# KitchenTimerFullDig.net
KiCad netlist of a schematic drawn in Altium Designer
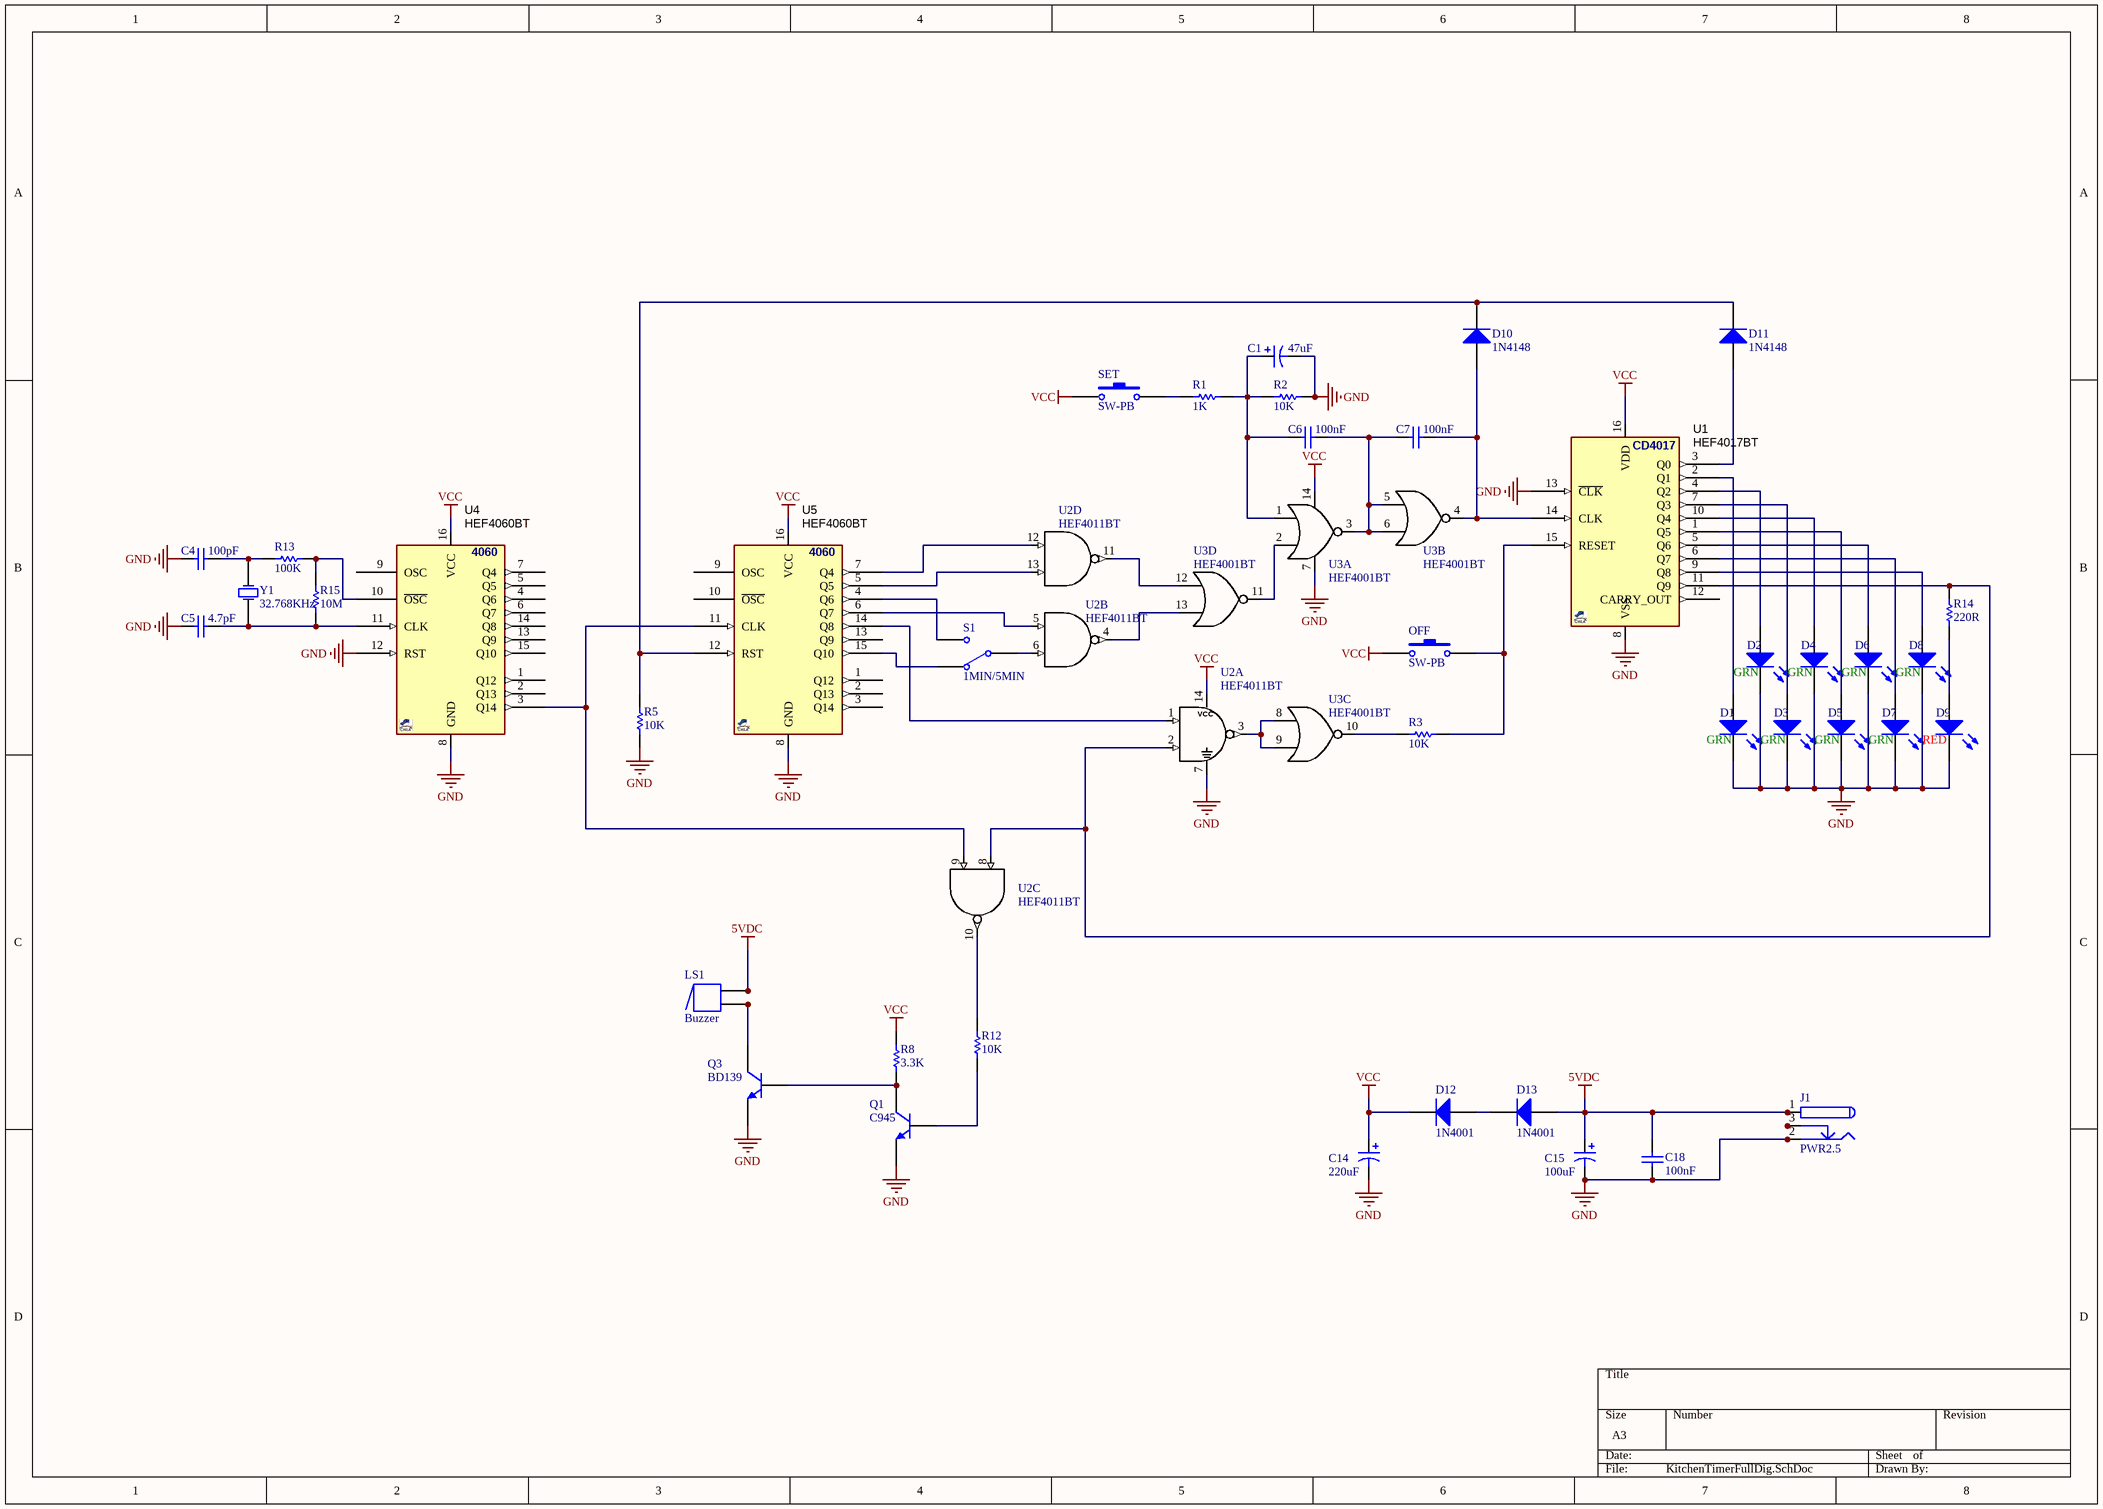
[diagram p0: KitchenTimerFullDig.SchDoc]

(export (version "E")
  (design (tool "Eeschema 10.0.6"))
  (components
    (comp (ref "C1")
      (value "47uF")
      (footprint "A")
      (description "Polarized Capacitor (Radial)")
      (fields (field (name "Comment") "Cap Pol1") (field (name "PUBLISHER") "Altium Limited"))
      (libsource (lib "Miscellaneous Devices") (part "Cap Pol1"))
    )
    (comp (ref "C4")
      (value "100pF")
      (footprint "CAP100N")
      (description "Capacitor")
      (fields (field (name "Comment") "Cap") (field (name "PUBLISHER") "Altium Limited"))
      (libsource (lib "Miscellaneous Devices") (part "Cap"))
    )
    (comp (ref "C5")
      (value "4.7pF")
      (footprint "CAP100N")
      (description "Capacitor")
      (fields (field (name "Comment") "Cap") (field (name "PUBLISHER") "Altium Limited"))
      (libsource (lib "Miscellaneous Devices") (part "Cap"))
    )
    (comp (ref "C6")
      (value "100nF")
      (footprint "CAP100N")
      (description "Capacitor")
      (fields (field (name "Comment") "Cap") (field (name "PUBLISHER") "Altium Limited"))
      (libsource (lib "Miscellaneous Devices") (part "Cap"))
    )
    (comp (ref "C7")
      (value "100nF")
      (footprint "CAP100N")
      (description "Capacitor")
      (fields (field (name "Comment") "Cap") (field (name "PUBLISHER") "Altium Limited"))
      (libsource (lib "Miscellaneous Devices") (part "Cap"))
    )
    (comp (ref "C14")
      (value "220uF")
      (footprint "A")
      (description "Polarized Capacitor (Radial)")
      (fields (field (name "Comment") "Cap Pol1") (field (name "PUBLISHER") "Altium Limited"))
      (libsource (lib "Miscellaneous Devices") (part "Cap Pol1"))
    )
    (comp (ref "C15")
      (value "100uF")
      (footprint "A")
      (description "Polarized Capacitor (Radial)")
      (fields (field (name "Comment") "Cap Pol1") (field (name "PUBLISHER") "Altium Limited"))
      (libsource (lib "Miscellaneous Devices") (part "Cap Pol1"))
    )
    (comp (ref "C18")
      (value "100nF")
      (footprint "CAP100N")
      (description "Capacitor")
      (fields (field (name "Comment") "Cap") (field (name "PUBLISHER") "Altium Limited"))
      (libsource (lib "Miscellaneous Devices") (part "Cap"))
    )
    (comp (ref "D1")
      (value "GRN")
      (footprint "LED3MM")
      (description "Typical INFRARED GaAs LED")
      (fields (field (name "PUBLISHER") "Altium Limited"))
      (libsource (lib "Miscellaneous Devices") (part "LED0"))
    )
    (comp (ref "D2")
      (value "GRN")
      (footprint "LED3MM")
      (description "Typical INFRARED GaAs LED")
      (fields (field (name "PUBLISHER") "Altium Limited"))
      (libsource (lib "Miscellaneous Devices") (part "LED0"))
    )
    (comp (ref "D3")
      (value "GRN")
      (footprint "LED3MM")
      (description "Typical INFRARED GaAs LED")
      (fields (field (name "PUBLISHER") "Altium Limited"))
      (libsource (lib "Miscellaneous Devices") (part "LED0"))
    )
    (comp (ref "D4")
      (value "GRN")
      (footprint "LED3MM")
      (description "Typical INFRARED GaAs LED")
      (fields (field (name "PUBLISHER") "Altium Limited"))
      (libsource (lib "Miscellaneous Devices") (part "LED0"))
    )
    (comp (ref "D5")
      (value "GRN")
      (footprint "LED3MM")
      (description "Typical INFRARED GaAs LED")
      (fields (field (name "PUBLISHER") "Altium Limited"))
      (libsource (lib "Miscellaneous Devices") (part "LED0"))
    )
    (comp (ref "D6")
      (value "GRN")
      (footprint "LED3MM")
      (description "Typical INFRARED GaAs LED")
      (fields (field (name "PUBLISHER") "Altium Limited"))
      (libsource (lib "Miscellaneous Devices") (part "LED0"))
    )
    (comp (ref "D7")
      (value "GRN")
      (footprint "LED3MM")
      (description "Typical INFRARED GaAs LED")
      (fields (field (name "PUBLISHER") "Altium Limited"))
      (libsource (lib "Miscellaneous Devices") (part "LED0"))
    )
    (comp (ref "D8")
      (value "GRN")
      (footprint "LED3MM")
      (description "Typical INFRARED GaAs LED")
      (fields (field (name "PUBLISHER") "Altium Limited"))
      (libsource (lib "Miscellaneous Devices") (part "LED0"))
    )
    (comp (ref "D9")
      (value "RED")
      (footprint "LED3MM")
      (description "Typical INFRARED GaAs LED")
      (fields (field (name "PUBLISHER") "Altium Limited"))
      (libsource (lib "Miscellaneous Devices") (part "LED0"))
    )
    (comp (ref "D10")
      (value "1N4148")
      (footprint "D_LN")
      (description "High Conductance Fast Diode")
      (fields (field (name "PUBLISHER") "Altium Limited"))
      (libsource (lib "Miscellaneous Devices") (part "Diode 1N4148"))
    )
    (comp (ref "D11")
      (value "1N4148")
      (footprint "D_LN")
      (description "High Conductance Fast Diode")
      (fields (field (name "PUBLISHER") "Altium Limited"))
      (libsource (lib "Miscellaneous Devices") (part "Diode 1N4148"))
    )
    (comp (ref "D12")
      (value "1N4001")
      (footprint "DO-35")
      (description "High Conductance Fast Diode")
      (fields (field (name "PUBLISHER") "Altium Limited"))
      (libsource (lib "Miscellaneous Devices") (part "Diode 1N4148"))
    )
    (comp (ref "D13")
      (value "1N4001")
      (footprint "DO-35")
      (description "High Conductance Fast Diode")
      (fields (field (name "PUBLISHER") "Altium Limited"))
      (libsource (lib "Miscellaneous Devices") (part "Diode 1N4148"))
    )
    (comp (ref "J1")
      (value "PWR2.5")
      (footprint "KLD-0202")
      (description "Low Voltage Power Supply Connector")
      (fields (field (name "PUBLISHER") "Altium Limited"))
      (libsource (lib "Miscellaneous Connectors") (part "PWR2.5"))
    )
    (comp (ref "LS1")
      (value "Buzzer")
      (footprint "ABSM-1574")
      (description "Magnetic Transducer Buzzer")
      (fields (field (name "PUBLISHER") "Altium Limited"))
      (libsource (lib "Miscellaneous Devices") (part "Buzzer"))
    )
    (comp (ref "OFF")
      (value "SW-PB")
      (footprint "BUTTN")
      (description "Switch")
      (fields (field (name "PUBLISHER") "Altium Limited"))
      (libsource (lib "Miscellaneous Devices") (part "SW-PB"))
    )
    (comp (ref "Q1")
      (value "C945")
      (footprint "TO-92")
      (description "NPN Bipolar Transistor")
      (fields (field (name "PUBLISHER") "Altium Limited"))
      (libsource (lib "Miscellaneous Devices") (part "NPN"))
    )
    (comp (ref "Q3")
      (value "BD139")
      (footprint "BD139")
      (description "NPN Bipolar Transistor")
      (fields (field (name "PUBLISHER") "Altium Limited"))
      (libsource (lib "Miscellaneous Devices") (part "NPN"))
    )
    (comp (ref "R1")
      (value "1K")
      (footprint "AXIAL-0.3")
      (description "Resistor")
      (fields (field (name "Comment") "Res1") (field (name "PUBLISHER") "Altium Limited"))
      (libsource (lib "Miscellaneous Devices") (part "Res1"))
    )
    (comp (ref "R2")
      (value "10K")
      (footprint "AXIAL-0.3")
      (description "Resistor")
      (fields (field (name "Comment") "Res1") (field (name "PUBLISHER") "Altium Limited"))
      (libsource (lib "Miscellaneous Devices") (part "Res1"))
    )
    (comp (ref "R3")
      (value "10K")
      (footprint "AXIAL-0.3")
      (description "Resistor")
      (fields (field (name "Comment") "Res1") (field (name "PUBLISHER") "Altium Limited"))
      (libsource (lib "Miscellaneous Devices") (part "Res1"))
    )
    (comp (ref "R5")
      (value "10K")
      (footprint "AXIAL-0.3")
      (description "Resistor")
      (fields (field (name "Comment") "Res1") (field (name "PUBLISHER") "Altium Limited"))
      (libsource (lib "Miscellaneous Devices") (part "Res1"))
    )
    (comp (ref "R8")
      (value "3.3K")
      (footprint "AXIAL-0.3")
      (description "Resistor")
      (fields (field (name "Comment") "Res1") (field (name "PUBLISHER") "Altium Limited"))
      (libsource (lib "Miscellaneous Devices") (part "Res1"))
    )
    (comp (ref "R12")
      (value "10K")
      (footprint "AXIAL-0.3")
      (description "Resistor")
      (fields (field (name "Comment") "Res1") (field (name "PUBLISHER") "Altium Limited"))
      (libsource (lib "Miscellaneous Devices") (part "Res1"))
    )
    (comp (ref "R13")
      (value "100K")
      (footprint "AXIAL-0.3")
      (description "Resistor")
      (fields (field (name "Comment") "Res1") (field (name "PUBLISHER") "Altium Limited"))
      (libsource (lib "Miscellaneous Devices") (part "Res1"))
    )
    (comp (ref "R14")
      (value "220R")
      (footprint "AXIAL-0.3")
      (description "Resistor")
      (fields (field (name "Comment") "Res1") (field (name "PUBLISHER") "Altium Limited"))
      (libsource (lib "Miscellaneous Devices") (part "Res1"))
    )
    (comp (ref "R15")
      (value "10M")
      (footprint "AXIAL-0.3")
      (description "Resistor")
      (fields (field (name "Comment") "Res1") (field (name "PUBLISHER") "Altium Limited"))
      (libsource (lib "Miscellaneous Devices") (part "Res1"))
    )
    (comp (ref "S1")
      (value "1MIN/5MIN")
      (footprint "TL36WW15050")
      (description "SPDT Subminiature Toggle Switch, Right Angle Mounting, Vertical Actuation")
      (fields (field (name "PUBLISHER") "Altium Limited"))
      (libsource (lib "Miscellaneous Devices") (part "SW-SPDT"))
    )
    (comp (ref "SET")
      (value "SW-PB")
      (footprint "BUTTN")
      (description "Switch")
      (fields (field (name "PUBLISHER") "Altium Limited"))
      (libsource (lib "Miscellaneous Devices") (part "SW-PB"))
    )
    (comp (ref "U1")
      (value "HEF4017BT")
      (footprint "SO_16")
      (description "Counter, 10 decoded output")
      (fields (field (name "MANF") "TI") (field (name "MANF_P#") "CD4017BE"))
      (libsource (lib "logic_counter") (part "CD4017_DIP16"))
    )
    (comp (ref "U2")
      (value "HEF4011BT")
      (footprint "SO_14")
      (description "GATE, NAND, Quad 2-Input")
      (fields (field (name "MANF_P#") "CD4011BCMA"))
      (libsource (lib "logic_gate") (part "NANDx4_CD4011BCM"))
    )
    (comp (ref "U3")
      (value "HEF4001BT")
      (footprint "SO_14")
      (description "Gate, NOR, Quad 2 Input")
      (fields (field (name "MANF") "Texas Instruments") (field (name "MANF_P#") "CD74HC02E"))
      (libsource (lib "KitchenTimerBoard") (part "NORx4_CD74HC02_DIP"))
    )
    (comp (ref "U4")
      (value "HEF4060BT")
      (footprint "SO_16")
      (description "Counter, 14-Bit Binary, 3~18v, 10mA")
      (fields (field (name "MANF") "TI") (field (name "MANF_P#") "CD4060BE"))
      (libsource (lib "logic_counter") (part "CD4060_DIP16"))
    )
    (comp (ref "U5")
      (value "HEF4060BT")
      (footprint "SO_16")
      (description "Counter, 14-Bit Binary, 3~18v, 10mA")
      (fields (field (name "MANF") "TI") (field (name "MANF_P#") "CD4060BE"))
      (libsource (lib "logic_counter") (part "CD4060_DIP16"))
    )
    (comp (ref "Y1")
      (value "32.768KHz")
      (footprint "XTAL")
      (description "Crystal Oscillator")
      (fields (field (name "Comment") "ECS-040-20-4X-DU") (field (name "PUBLISHER") "Altium Limited"))
      (libsource (lib "AXC-WS1") (part "XTAL"))
    )
  )
  (nets
    (net (code "1") (name "5VDC") (class "Default")
      (node (ref "C15") (pin "1") (pinfunction "1_1") (pintype "passive"))
      (node (ref "C18") (pin "2") (pinfunction "2_2") (pintype "passive"))
      (node (ref "D13") (pin "1") (pinfunction "A_1") (pintype "passive"))
      (node (ref "J1") (pin "1") (pinfunction "1_1") (pintype "power_in"))
      (node (ref "J1") (pin "1A") (pinfunction "1A_1A") (pintype "power_in"))
      (node (ref "J1") (pin "1B") (pinfunction "1B_1B") (pintype "power_in"))
      (node (ref "LS1") (pin "1") (pinfunction "1_1") (pintype "passive"))
      (node (ref "LS1") (pin "1A") (pinfunction "1A_1A") (pintype "passive"))
    )
    (net (code "2") (name "GND") (class "Default")
      (node (ref "C1") (pin "2") (pinfunction "2_2") (pintype "passive"))
      (node (ref "C14") (pin "2") (pinfunction "2_2") (pintype "passive"))
      (node (ref "C15") (pin "2") (pinfunction "2_2") (pintype "passive"))
      (node (ref "C18") (pin "1") (pinfunction "1_1") (pintype "passive"))
      (node (ref "C4") (pin "1") (pinfunction "1_1") (pintype "passive"))
      (node (ref "C5") (pin "1") (pinfunction "1_1") (pintype "passive"))
      (node (ref "D1") (pin "2") (pinfunction "K_2") (pintype "passive"))
      (node (ref "D2") (pin "2") (pinfunction "K_2") (pintype "passive"))
      (node (ref "D3") (pin "2") (pinfunction "K_2") (pintype "passive"))
      (node (ref "D4") (pin "2") (pinfunction "K_2") (pintype "passive"))
      (node (ref "D5") (pin "2") (pinfunction "K_2") (pintype "passive"))
      (node (ref "D6") (pin "2") (pinfunction "K_2") (pintype "passive"))
      (node (ref "D7") (pin "2") (pinfunction "K_2") (pintype "passive"))
      (node (ref "D8") (pin "2") (pinfunction "K_2") (pintype "passive"))
      (node (ref "D9") (pin "2") (pinfunction "K_2") (pintype "passive"))
      (node (ref "J1") (pin "2") (pinfunction "2_2") (pintype "power_in"))
      (node (ref "J1") (pin "2A") (pinfunction "2A_2A") (pintype "power_in"))
      (node (ref "J1") (pin "2B") (pinfunction "2B_2B") (pintype "power_in"))
      (node (ref "Q1") (pin "3") (pinfunction "E_3") (pintype "passive"))
      (node (ref "Q3") (pin "3") (pinfunction "E_3") (pintype "passive"))
      (node (ref "R2") (pin "2") (pinfunction "2_2") (pintype "passive"))
      (node (ref "R5") (pin "2") (pinfunction "2_2") (pintype "passive"))
      (node (ref "U1") (pin "13") (pinfunction "~{CLK}_13") (pintype "input"))
      (node (ref "U1") (pin "8") (pinfunction "VSS_8") (pintype "power_in"))
      (node (ref "U2") (pin "7") (pinfunction "GND_7") (pintype "power_in"))
      (node (ref "U3") (pin "7") (pinfunction "GND_7") (pintype "passive"))
      (node (ref "U4") (pin "12") (pinfunction "RST_12") (pintype "input"))
      (node (ref "U4") (pin "8") (pinfunction "GND_8") (pintype "power_in"))
      (node (ref "U5") (pin "8") (pinfunction "GND_8") (pintype "power_in"))
    )
    (net (code "3") (name "Net-(C1-Pad1)") (class "Default")
      (node (ref "C1") (pin "1") (pinfunction "1_1") (pintype "passive"))
      (node (ref "C6") (pin "1") (pinfunction "1_1") (pintype "passive"))
      (node (ref "R1") (pin "2") (pinfunction "2_2") (pintype "passive"))
      (node (ref "R2") (pin "1") (pinfunction "1_1") (pintype "passive"))
      (node (ref "U3") (pin "1") (pinfunction "1_1") (pintype "passive"))
    )
    (net (code "4") (name "Net-(C6-Pad2)") (class "Default")
      (node (ref "C6") (pin "2") (pinfunction "2_2") (pintype "passive"))
      (node (ref "C7") (pin "1") (pinfunction "1_1") (pintype "passive"))
      (node (ref "U3") (pin "3") (pinfunction "3_3") (pintype "passive"))
      (node (ref "U3") (pin "5") (pinfunction "5_5") (pintype "passive"))
      (node (ref "U3") (pin "6") (pinfunction "6_6") (pintype "passive"))
    )
    (net (code "5") (name "Net-(D1-A)") (class "Default")
      (node (ref "D1") (pin "1") (pinfunction "A_1") (pintype "passive"))
      (node (ref "U1") (pin "2") (pinfunction "Q1_2") (pintype "output"))
    )
    (net (code "6") (name "Net-(D2-A)") (class "Default")
      (node (ref "D2") (pin "1") (pinfunction "A_1") (pintype "passive"))
      (node (ref "U1") (pin "4") (pinfunction "Q2_4") (pintype "output"))
    )
    (net (code "7") (name "Net-(D3-A)") (class "Default")
      (node (ref "D3") (pin "1") (pinfunction "A_1") (pintype "passive"))
      (node (ref "U1") (pin "7") (pinfunction "Q3_7") (pintype "output"))
    )
    (net (code "8") (name "Net-(D4-A)") (class "Default")
      (node (ref "D4") (pin "1") (pinfunction "A_1") (pintype "passive"))
      (node (ref "U1") (pin "10") (pinfunction "Q4_10") (pintype "output"))
    )
    (net (code "9") (name "Net-(D5-A)") (class "Default")
      (node (ref "D5") (pin "1") (pinfunction "A_1") (pintype "passive"))
      (node (ref "U1") (pin "1") (pinfunction "Q5_1") (pintype "output"))
    )
    (net (code "10") (name "Net-(D6-A)") (class "Default")
      (node (ref "D6") (pin "1") (pinfunction "A_1") (pintype "passive"))
      (node (ref "U1") (pin "5") (pinfunction "Q6_5") (pintype "output"))
    )
    (net (code "11") (name "Net-(D7-A)") (class "Default")
      (node (ref "D7") (pin "1") (pinfunction "A_1") (pintype "passive"))
      (node (ref "U1") (pin "6") (pinfunction "Q7_6") (pintype "output"))
    )
    (net (code "12") (name "Net-(D8-A)") (class "Default")
      (node (ref "D8") (pin "1") (pinfunction "A_1") (pintype "passive"))
      (node (ref "U1") (pin "9") (pinfunction "Q8_9") (pintype "output"))
    )
    (net (code "13") (name "Net-(D9-A)") (class "Default")
      (node (ref "D9") (pin "1") (pinfunction "A_1") (pintype "passive"))
      (node (ref "R14") (pin "1") (pinfunction "1_1") (pintype "passive"))
    )
    (net (code "14") (name "Net-(D10-A)") (class "Default")
      (node (ref "C7") (pin "2") (pinfunction "2_2") (pintype "passive"))
      (node (ref "D10") (pin "1") (pinfunction "A_1") (pintype "passive"))
      (node (ref "U1") (pin "14") (pinfunction "CLK_14") (pintype "input"))
      (node (ref "U3") (pin "4") (pinfunction "4_4") (pintype "passive"))
    )
    (net (code "15") (name "Net-(D10-K)") (class "Default")
      (node (ref "D10") (pin "2") (pinfunction "K_2") (pintype "passive"))
      (node (ref "D11") (pin "2") (pinfunction "K_2") (pintype "passive"))
      (node (ref "R5") (pin "1") (pinfunction "1_1") (pintype "passive"))
      (node (ref "U5") (pin "12") (pinfunction "RST_12") (pintype "input"))
    )
    (net (code "16") (name "Net-(D11-A)") (class "Default")
      (node (ref "D11") (pin "1") (pinfunction "A_1") (pintype "passive"))
      (node (ref "U1") (pin "3") (pinfunction "Q0_3") (pintype "output"))
    )
    (net (code "17") (name "Net-(D12-A)") (class "Default")
      (node (ref "D12") (pin "1") (pinfunction "A_1") (pintype "passive"))
      (node (ref "D13") (pin "2") (pinfunction "K_2") (pintype "passive"))
    )
    (net (code "18") (name "Net-(J1-Pad3)") (class "Default")
      (node (ref "J1") (pin "3") (pinfunction "3_3") (pintype "power_in"))
      (node (ref "J1") (pin "3A") (pinfunction "3A_3A") (pintype "power_in"))
      (node (ref "J1") (pin "3B") (pinfunction "3B_3B") (pintype "power_in"))
    )
    (net (code "19") (name "Net-(Q1-B)") (class "Default")
      (node (ref "Q1") (pin "2") (pinfunction "B_2") (pintype "passive"))
      (node (ref "R12") (pin "2") (pinfunction "2_2") (pintype "passive"))
    )
    (net (code "20") (name "Net-(Q1-C)") (class "Default")
      (node (ref "Q1") (pin "1") (pinfunction "C_1") (pintype "passive"))
      (node (ref "Q3") (pin "2") (pinfunction "B_2") (pintype "passive"))
      (node (ref "R8") (pin "1") (pinfunction "1_1") (pintype "passive"))
    )
    (net (code "21") (name "Net-(Q3-C)") (class "Default")
      (node (ref "LS1") (pin "2") (pinfunction "2_2") (pintype "passive"))
      (node (ref "LS1") (pin "2A") (pinfunction "2A_2A") (pintype "passive"))
      (node (ref "Q3") (pin "1") (pinfunction "C_1") (pintype "passive"))
    )
    (net (code "22") (name "Net-(R1-Pad1)") (class "Default")
      (node (ref "R1") (pin "1") (pinfunction "1_1") (pintype "passive"))
      (node (ref "SET") (pin "1") (pinfunction "1_1") (pintype "passive"))
    )
    (net (code "23") (name "Net-(R3-Pad1)") (class "Default")
      (node (ref "R3") (pin "1") (pinfunction "1_1") (pintype "passive"))
      (node (ref "U3") (pin "10") (pinfunction "10_10") (pintype "passive"))
    )
    (net (code "24") (name "Net-(U1-Q9)") (class "Default")
      (node (ref "R14") (pin "2") (pinfunction "2_2") (pintype "passive"))
      (node (ref "U1") (pin "11") (pinfunction "Q9_11") (pintype "output"))
      (node (ref "U2") (pin "2") (pinfunction "B_2") (pintype "input"))
      (node (ref "U2") (pin "8") (pinfunction "A_8") (pintype "input"))
    )
    (net (code "25") (name "Net-(U1-RESET)") (class "Default")
      (node (ref "OFF") (pin "2") (pinfunction "2_2") (pintype "passive"))
      (node (ref "R3") (pin "2") (pinfunction "2_2") (pintype "passive"))
      (node (ref "U1") (pin "15") (pinfunction "RESET_15") (pintype "input"))
    )
    (net (code "26") (name "Net-(U2A-A)") (class "Default")
      (node (ref "U2") (pin "1") (pinfunction "A_1") (pintype "input"))
      (node (ref "U5") (pin "14") (pinfunction "Q8_14") (pintype "output"))
    )
    (net (code "27") (name "Net-(U2A-J)") (class "Default")
      (node (ref "U2") (pin "3") (pinfunction "J_3") (pintype "output"))
      (node (ref "U3") (pin "8") (pinfunction "8_8") (pintype "passive"))
      (node (ref "U3") (pin "9") (pinfunction "9_9") (pintype "passive"))
    )
    (net (code "28") (name "Net-(U2B-A)") (class "Default")
      (node (ref "U2") (pin "5") (pinfunction "A_5") (pintype "input"))
      (node (ref "U5") (pin "6") (pinfunction "Q7_6") (pintype "output"))
    )
    (net (code "29") (name "Net-(U2B-B)") (class "Default")
      (node (ref "S1") (pin "2") (pinfunction "2_2") (pintype "passive"))
      (node (ref "U2") (pin "6") (pinfunction "B_6") (pintype "input"))
    )
    (net (code "30") (name "Net-(U2B-J)") (class "Default")
      (node (ref "U2") (pin "4") (pinfunction "J_4") (pintype "output"))
      (node (ref "U3") (pin "13") (pinfunction "13_13") (pintype "passive"))
    )
    (net (code "31") (name "Net-(U2C-F)") (class "Default")
      (node (ref "U2") (pin "9") (pinfunction "F_9") (pintype "input"))
      (node (ref "U4") (pin "3") (pinfunction "Q14_3") (pintype "output"))
      (node (ref "U5") (pin "11") (pinfunction "CLK_11") (pintype "input"))
    )
    (net (code "32") (name "Net-(U2C-J)") (class "Default")
      (node (ref "R12") (pin "1") (pinfunction "1_1") (pintype "passive"))
      (node (ref "U2") (pin "10") (pinfunction "J_10") (pintype "output"))
    )
    (net (code "33") (name "Net-(U2D-A)") (class "Default")
      (node (ref "U2") (pin "12") (pinfunction "A_12") (pintype "input"))
      (node (ref "U5") (pin "7") (pinfunction "Q4_7") (pintype "output"))
    )
    (net (code "34") (name "Net-(U2D-B)") (class "Default")
      (node (ref "U2") (pin "13") (pinfunction "B_13") (pintype "input"))
      (node (ref "U5") (pin "5") (pinfunction "Q5_5") (pintype "output"))
    )
    (net (code "35") (name "Net-(U2D-J)") (class "Default")
      (node (ref "U2") (pin "11") (pinfunction "J_11") (pintype "output"))
      (node (ref "U3") (pin "12") (pinfunction "12_12") (pintype "passive"))
    )
    (net (code "36") (name "Net-(U3-Pad11)") (class "Default")
      (node (ref "U3") (pin "11") (pinfunction "11_11") (pintype "passive"))
      (node (ref "U3") (pin "2") (pinfunction "2_2") (pintype "passive"))
    )
    (net (code "37") (name "Net-(U4-CLK)") (class "Default")
      (node (ref "C5") (pin "2") (pinfunction "2_2") (pintype "passive"))
      (node (ref "R15") (pin "1") (pinfunction "1_1") (pintype "passive"))
      (node (ref "U4") (pin "11") (pinfunction "CLK_11") (pintype "input"))
      (node (ref "Y1") (pin "2") (pinfunction "OSC2_2") (pintype "passive"))
    )
    (net (code "38") (name "Net-(U4-~{OSC})") (class "Default")
      (node (ref "R13") (pin "2") (pinfunction "2_2") (pintype "passive"))
      (node (ref "R15") (pin "2") (pinfunction "2_2") (pintype "passive"))
      (node (ref "U4") (pin "10") (pinfunction "~{OSC}_10") (pintype "passive"))
    )
    (net (code "39") (name "Net-(U5-Q6)") (class "Default")
      (node (ref "S1") (pin "1") (pinfunction "1_1") (pintype "passive"))
      (node (ref "U5") (pin "4") (pinfunction "Q6_4") (pintype "output"))
    )
    (net (code "40") (name "Net-(U5-Q10)") (class "Default")
      (node (ref "S1") (pin "3") (pinfunction "3_3") (pintype "passive"))
      (node (ref "U5") (pin "15") (pinfunction "Q10_15") (pintype "output"))
    )
    (net (code "41") (name "Net-(Y1-OSC1)") (class "Default")
      (node (ref "C4") (pin "2") (pinfunction "2_2") (pintype "passive"))
      (node (ref "R13") (pin "1") (pinfunction "1_1") (pintype "passive"))
      (node (ref "Y1") (pin "1") (pinfunction "OSC1_1") (pintype "passive"))
    )
    (net (code "42") (name "VCC") (class "Default")
      (node (ref "C14") (pin "1") (pinfunction "1_1") (pintype "passive"))
      (node (ref "D12") (pin "2") (pinfunction "K_2") (pintype "passive"))
      (node (ref "OFF") (pin "1") (pinfunction "1_1") (pintype "passive"))
      (node (ref "R8") (pin "2") (pinfunction "2_2") (pintype "passive"))
      (node (ref "SET") (pin "2") (pinfunction "2_2") (pintype "passive"))
      (node (ref "U1") (pin "16") (pinfunction "VDD_16") (pintype "power_in"))
      (node (ref "U2") (pin "14") (pinfunction "VDD_14") (pintype "power_in"))
      (node (ref "U3") (pin "14") (pinfunction "VCC_14") (pintype "passive"))
      (node (ref "U4") (pin "16") (pinfunction "VCC_16") (pintype "power_in"))
      (node (ref "U5") (pin "16") (pinfunction "VCC_16") (pintype "power_in"))
    )
    (net (code "43") (name "unconnected-(U1-CARRY_OUT-Pad12)") (class "Default")
      (node (ref "U1") (pin "12") (pinfunction "CARRY_OUT_12") (pintype "output"))
    )
    (net (code "44") (name "unconnected-(U4-OSC-Pad9)") (class "Default")
      (node (ref "U4") (pin "9") (pinfunction "OSC_9") (pintype "passive"))
    )
    (net (code "45") (name "unconnected-(U4-Q4-Pad7)") (class "Default")
      (node (ref "U4") (pin "7") (pinfunction "Q4_7") (pintype "output"))
    )
    (net (code "46") (name "unconnected-(U4-Q5-Pad5)") (class "Default")
      (node (ref "U4") (pin "5") (pinfunction "Q5_5") (pintype "output"))
    )
    (net (code "47") (name "unconnected-(U4-Q6-Pad4)") (class "Default")
      (node (ref "U4") (pin "4") (pinfunction "Q6_4") (pintype "output"))
    )
    (net (code "48") (name "unconnected-(U4-Q7-Pad6)") (class "Default")
      (node (ref "U4") (pin "6") (pinfunction "Q7_6") (pintype "output"))
    )
    (net (code "49") (name "unconnected-(U4-Q8-Pad14)") (class "Default")
      (node (ref "U4") (pin "14") (pinfunction "Q8_14") (pintype "output"))
    )
    (net (code "50") (name "unconnected-(U4-Q9-Pad13)") (class "Default")
      (node (ref "U4") (pin "13") (pinfunction "Q9_13") (pintype "output"))
    )
    (net (code "51") (name "unconnected-(U4-Q10-Pad15)") (class "Default")
      (node (ref "U4") (pin "15") (pinfunction "Q10_15") (pintype "output"))
    )
    (net (code "52") (name "unconnected-(U4-Q12-Pad1)") (class "Default")
      (node (ref "U4") (pin "1") (pinfunction "Q12_1") (pintype "output"))
    )
    (net (code "53") (name "unconnected-(U4-Q13-Pad2)") (class "Default")
      (node (ref "U4") (pin "2") (pinfunction "Q13_2") (pintype "output"))
    )
    (net (code "54") (name "unconnected-(U5-OSC-Pad9)") (class "Default")
      (node (ref "U5") (pin "9") (pinfunction "OSC_9") (pintype "passive"))
    )
    (net (code "55") (name "unconnected-(U5-Q9-Pad13)") (class "Default")
      (node (ref "U5") (pin "13") (pinfunction "Q9_13") (pintype "output"))
    )
    (net (code "56") (name "unconnected-(U5-Q12-Pad1)") (class "Default")
      (node (ref "U5") (pin "1") (pinfunction "Q12_1") (pintype "output"))
    )
    (net (code "57") (name "unconnected-(U5-Q13-Pad2)") (class "Default")
      (node (ref "U5") (pin "2") (pinfunction "Q13_2") (pintype "output"))
    )
    (net (code "58") (name "unconnected-(U5-Q14-Pad3)") (class "Default")
      (node (ref "U5") (pin "3") (pinfunction "Q14_3") (pintype "output"))
    )
    (net (code "59") (name "unconnected-(U5-~{OSC}-Pad10)") (class "Default")
      (node (ref "U5") (pin "10") (pinfunction "~{OSC}_10") (pintype "passive"))
    )
  )
)
